# Schematic.net
KiCad netlist of a schematic drawn in Altium Designer
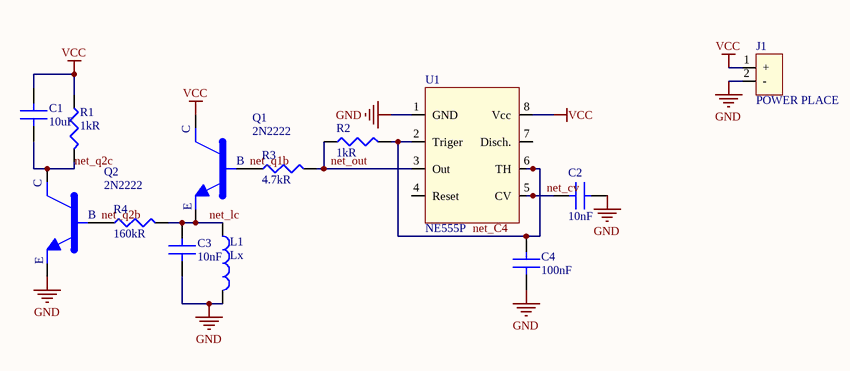
[diagram p0: Schematic.SchDoc]

(export (version "E")
  (design (tool "Eeschema 10.0.6"))
  (components
    (comp (ref "C1")
      (value "10uF")
      (footprint "C0805")
      (description "Cap Ceramic 10uF 16V X5R 10% SMD 0805 85C Cardboard T/R")
      (fields
        (field (name "MANUFACTURER") "Samsung")
        (field (name "MANUFACTURER PART NUMBER") "CL21A106KOCLRNC")
      )
      (libsource (lib "Schlib") (part "Cap_0805_10u"))
    )
    (comp (ref "C2")
      (value "10nF")
      (footprint "C0805")
      (description "Cap Ceramic 0.01uF 25V X7R 10% Pad SMD 0805 125°C T/R")
      (fields
        (field (name "MANUFACTURER") "Samsung")
        (field (name "MANUFACTURER PART NUMBER") "CL21B103KAANNNC")
      )
      (libsource (lib "Schlib") (part "Cap_0805_10n"))
    )
    (comp (ref "C3")
      (value "10nF")
      (footprint "C0805")
      (description "Cap Ceramic 0.01uF 25V X7R 10% Pad SMD 0805 125°C T/R")
      (fields
        (field (name "MANUFACTURER") "Samsung")
        (field (name "MANUFACTURER PART NUMBER") "CL21B103KAANNNC")
      )
      (libsource (lib "Schlib") (part "Cap_0805_10n"))
    )
    (comp (ref "C4")
      (value "100nF")
      (footprint "C0805")
      (fields
        (field (name "MANUFACTURER") "Walsin Technologies")
        (field (name "MANUFACTURER PART NUMBER") "0805B104K160CT")
        (field (name "TOLERANCE") "10%")
      )
      (libsource (lib "Schlib") (part "Cap_0805_100n"))
    )
    (comp (ref "J1")
      (value "POWER PLACE")
      (footprint "poweplc")
      (libsource (lib "Schlib") (part "POWER PLACE"))
    )
    (comp (ref "L1") (value "Lx") (footprint "LX") (libsource (lib "Schlib") (part "Lx")))
    (comp (ref "Q1")
      (value "2N2222")
      (footprint "2N2222SMD")
      (fields
        (field (name "MANUFACTURER") "ON Semiconductor")
        (field (name "MANUFACTURER PART NUMBER") "SMMBT2222ALT1G")
      )
      (libsource (lib "Schlib") (part "SMMBT2222ALT1G"))
    )
    (comp (ref "Q2")
      (value "2N2222")
      (footprint "2N2222SMD")
      (fields
        (field (name "MANUFACTURER") "ON Semiconductor")
        (field (name "MANUFACTURER PART NUMBER") "SMMBT2222ALT1G")
      )
      (libsource (lib "Schlib") (part "SMMBT2222ALT1G"))
    )
    (comp (ref "R1")
      (value "1kR")
      (footprint "R0805")
      (fields
        (field (name "MANUFACTURER") "KOA Speer")
        (field (name "MANUFACTURER PART NUMBER") "RK73H2ATTD1001F")
        (field (name "TOLERANCE") "1%")
      )
      (libsource (lib "Schlib") (part "Res_0805_1k"))
    )
    (comp (ref "R2")
      (value "1kR")
      (footprint "R0805")
      (fields
        (field (name "MANUFACTURER") "KOA Speer")
        (field (name "MANUFACTURER PART NUMBER") "RK73H2ATTD1001F")
        (field (name "TOLERANCE") "1%")
      )
      (libsource (lib "Schlib") (part "Res_0805_1k"))
    )
    (comp (ref "R3")
      (value "4.7kR")
      (footprint "R0805")
      (description "Res Thick Film 0805 4.7K Ohm 1% 0.25W(1/4W) ±100ppm/C Pad SMD Automotive T/R")
      (fields
        (field (name "MANUFACTURER") "KOA Speer")
        (field (name "MANUFACTURER PART NUMBER") "RK73H2ATTD4701F")
      )
      (libsource (lib "Schlib") (part "Res_0805_4.7k"))
    )
    (comp (ref "R4")
      (value "160kR")
      (footprint "R0805")
      (description "Thick Film Resistors - SMD 0805 160Kohms 1% Tol")
      (fields
        (field (name "MANUFACTURER") "Panasonic")
        (field (name "MANUFACTURER PART NUMBER") "ERJ-6ENF1603V")
      )
      (libsource (lib "Schlib") (part "Res_0805_160k"))
    )
    (comp (ref "U1")
      (value "NE555P")
      (footprint "NE555")
      (description "Standard Timer Single 8-Pin PDIP Tube")
      (fields (field (name "MANUFACTURER") "Texas Instruments"))
      (libsource (lib "Schlib") (part "NE555P"))
    )
  )
  (nets
    (net (code "1") (name "/net_C4") (class "Default")
      (node (ref "C4") (pin "1") (pinfunction "1_1") (pintype "passive"))
      (node (ref "R2") (pin "1") (pinfunction "1_1") (pintype "passive"))
      (node (ref "U1") (pin "2") (pinfunction "Triger_2") (pintype "passive"))
      (node (ref "U1") (pin "6") (pinfunction "TH_6") (pintype "passive"))
    )
    (net (code "2") (name "/net_cv") (class "Default")
      (node (ref "C2") (pin "1") (pinfunction "1_1") (pintype "passive"))
      (node (ref "U1") (pin "5") (pinfunction "CV_5") (pintype "passive"))
    )
    (net (code "3") (name "/net_lc") (class "Default")
      (node (ref "C3") (pin "2") (pinfunction "2_2") (pintype "passive"))
      (node (ref "L1") (pin "1") (pinfunction "1_1") (pintype "passive"))
      (node (ref "Q1") (pin "2") (pinfunction "E_2") (pintype "passive"))
      (node (ref "R4") (pin "1") (pinfunction "1_1") (pintype "passive"))
    )
    (net (code "4") (name "/net_out") (class "Default")
      (node (ref "R2") (pin "2") (pinfunction "2_2") (pintype "passive"))
      (node (ref "R3") (pin "1") (pinfunction "1_1") (pintype "passive"))
      (node (ref "U1") (pin "3") (pinfunction "Out_3") (pintype "passive"))
    )
    (net (code "5") (name "/net_q1b") (class "Default")
      (node (ref "Q1") (pin "1") (pinfunction "B_1") (pintype "passive"))
      (node (ref "R3") (pin "2") (pinfunction "2_2") (pintype "passive"))
    )
    (net (code "6") (name "/net_q2b") (class "Default")
      (node (ref "Q2") (pin "1") (pinfunction "B_1") (pintype "passive"))
      (node (ref "R4") (pin "2") (pinfunction "2_2") (pintype "passive"))
    )
    (net (code "7") (name "/net_q2c") (class "Default")
      (node (ref "C1") (pin "1") (pinfunction "1_1") (pintype "passive"))
      (node (ref "Q2") (pin "3") (pinfunction "C_3") (pintype "passive"))
      (node (ref "R1") (pin "1") (pinfunction "1_1") (pintype "passive"))
    )
    (net (code "8") (name "GND") (class "Default")
      (node (ref "C2") (pin "2") (pinfunction "2_2") (pintype "passive"))
      (node (ref "C3") (pin "1") (pinfunction "1_1") (pintype "passive"))
      (node (ref "C4") (pin "2") (pinfunction "2_2") (pintype "passive"))
      (node (ref "J1") (pin "2") (pinfunction "-_2") (pintype "passive"))
      (node (ref "L1") (pin "2") (pinfunction "2_2") (pintype "passive"))
      (node (ref "Q2") (pin "2") (pinfunction "E_2") (pintype "passive"))
      (node (ref "U1") (pin "1") (pinfunction "GND_1") (pintype "passive"))
    )
    (net (code "9") (name "VCC") (class "Default")
      (node (ref "C1") (pin "2") (pinfunction "2_2") (pintype "passive"))
      (node (ref "J1") (pin "1") (pinfunction "+_1") (pintype "passive"))
      (node (ref "Q1") (pin "3") (pinfunction "C_3") (pintype "passive"))
      (node (ref "R1") (pin "2") (pinfunction "2_2") (pintype "passive"))
      (node (ref "U1") (pin "8") (pinfunction "Vcc_8") (pintype "passive"))
    )
    (net (code "10") (name "unconnected-(U1-Disch.-Pad7)") (class "Default")
      (node (ref "U1") (pin "7") (pinfunction "Disch._7") (pintype "passive"))
    )
    (net (code "11") (name "unconnected-(U1-Reset-Pad4)") (class "Default")
      (node (ref "U1") (pin "4") (pinfunction "Reset_4") (pintype "passive"))
    )
  )
)
